# led-controller.net
KiCad netlist of a schematic drawn in EAGLE
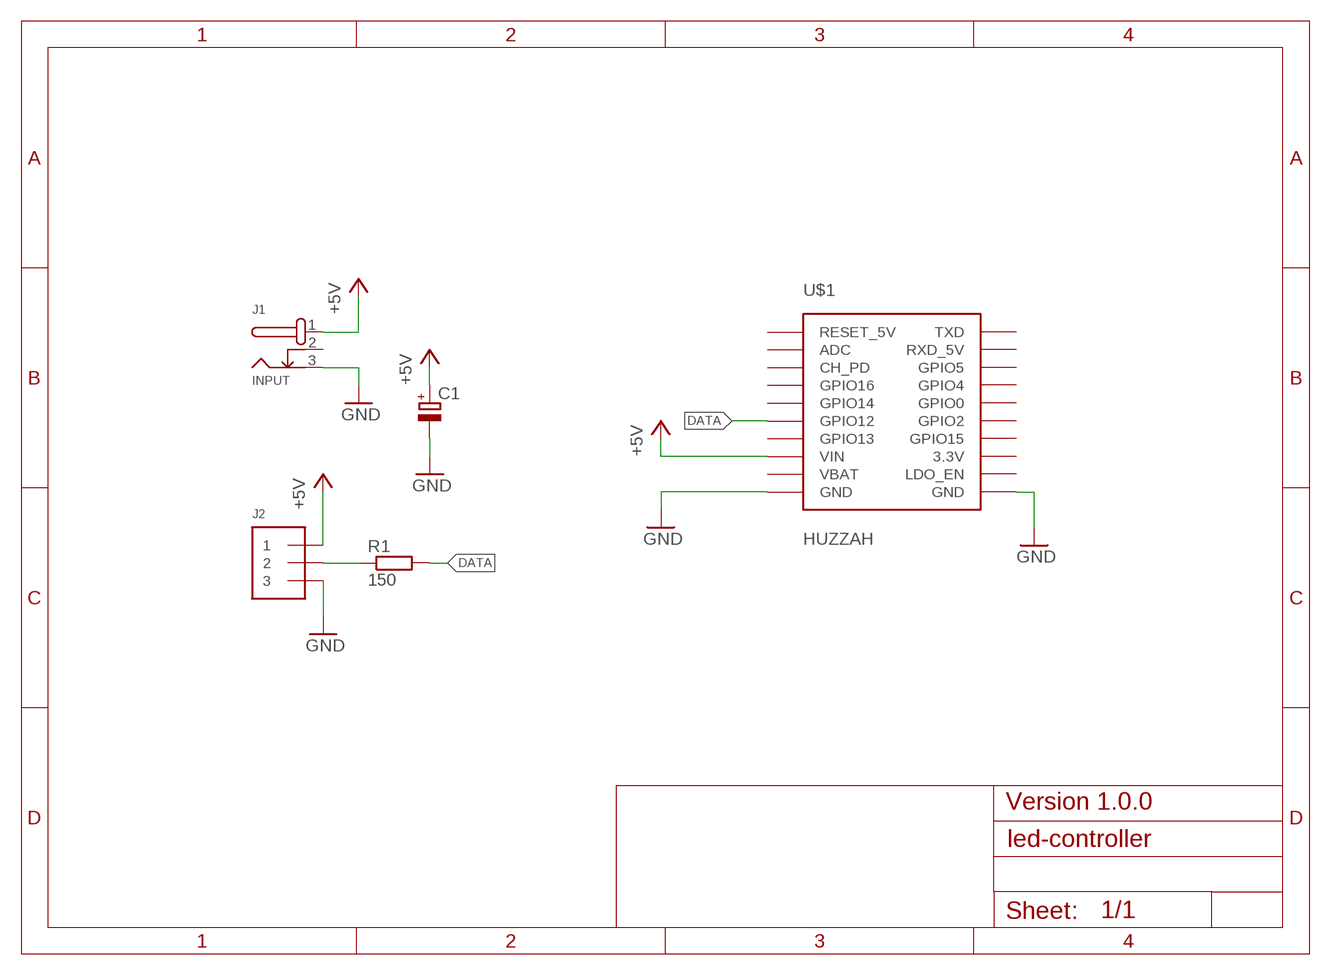
[diagram p0: schematic, sheet 1]

(export (version "E")
  (design (tool "Eeschema 10.0.6"))
  (components
    (comp (ref "C1")
      (value "CPOL-EUE7.5-16")
      (footprint "eagle-import:E7,5-16")
      (libsource (lib "eagle-import") (part "CPOL-EUE7.5-16"))
    )
    (comp (ref "J1")
      (value "INPUT")
      (footprint "eagle-import:DC10")
      (libsource (lib "eagle-import") (part "DC10PTH"))
    )
    (comp (ref "J2")
      (value "3,5MM-1X3-TERMBLOCK")
      (footprint "eagle-import:3,5MM-1X3-TERMBLOCK")
      (libsource (lib "eagle-import") (part "3,5MM-1X3-TERMBLOCK"))
    )
    (comp (ref "R1")
      (value "150")
      (footprint "eagle-import:R1206W")
      (libsource (lib "eagle-import") (part "R-EU_R1206W"))
    )
    (comp (ref "U$1")
      (value "HUZZAH")
      (footprint "eagle-import:HUZZAH")
      (libsource (lib "eagle-import") (part "HUZZAH"))
    )
  )
  (nets
    (net (code "1") (name "+5V") (class "Default")
      (node (ref "C1") (pin "+") (pinfunction "+_+") (pintype "passive"))
      (node (ref "J1") (pin "1") (pinfunction "1_1") (pintype "power_in"))
      (node (ref "J2") (pin "1") (pinfunction "1_1") (pintype "bidirectional"))
      (node (ref "U$1") (pin "VIN") (pinfunction "VIN_VIN") (pintype "bidirectional"))
    )
    (net (code "2") (name "/2") (class "Default")
      (node (ref "J1") (pin "2") (pinfunction "2_2") (pintype "power_in"))
    )
    (net (code "3") (name "DATA") (class "Default")
      (node (ref "R1") (pin "2") (pinfunction "2_2") (pintype "passive"))
      (node (ref "U$1") (pin "GPIO12") (pinfunction "GPIO12_GPIO12") (pintype "bidirectional"))
    )
    (net (code "4") (name "GND") (class "Default")
      (node (ref "C1") (pin "-") (pinfunction "-_-") (pintype "passive"))
      (node (ref "J1") (pin "3") (pinfunction "3_3") (pintype "power_in"))
      (node (ref "J2") (pin "3") (pinfunction "3_3") (pintype "bidirectional"))
      (node (ref "U$1") (pin "GND@1") (pinfunction "GND_GND@1") (pintype "bidirectional"))
      (node (ref "U$1") (pin "GND@2") (pinfunction "GND_GND@2") (pintype "bidirectional"))
    )
    (net (code "5") (name "Net-(J2-Pad2)") (class "Default")
      (node (ref "J2") (pin "2") (pinfunction "2_2") (pintype "bidirectional"))
      (node (ref "R1") (pin "1") (pinfunction "1_1") (pintype "passive"))
    )
    (net (code "6") (name "unconnected-(U$1-Pad3.3V)") (class "Default")
      (node (ref "U$1") (pin "3.3V") (pinfunction "3.3V_3.3V") (pintype "bidirectional"))
    )
    (net (code "7") (name "unconnected-(U$1-PadADC)") (class "Default")
      (node (ref "U$1") (pin "ADC") (pinfunction "ADC_ADC") (pintype "bidirectional"))
    )
    (net (code "8") (name "unconnected-(U$1-PadCH_PD)") (class "Default")
      (node (ref "U$1") (pin "CH_PD") (pinfunction "CH_PD_CH_PD") (pintype "bidirectional"))
    )
    (net (code "9") (name "unconnected-(U$1-PadGPIO0)") (class "Default")
      (node (ref "U$1") (pin "GPIO0") (pinfunction "GPIO0_GPIO0") (pintype "bidirectional"))
    )
    (net (code "10") (name "unconnected-(U$1-PadGPIO2)") (class "Default")
      (node (ref "U$1") (pin "GPIO2") (pinfunction "GPIO2_GPIO2") (pintype "bidirectional"))
    )
    (net (code "11") (name "unconnected-(U$1-PadGPIO4)") (class "Default")
      (node (ref "U$1") (pin "GPIO4") (pinfunction "GPIO4_GPIO4") (pintype "bidirectional"))
    )
    (net (code "12") (name "unconnected-(U$1-PadGPIO5)") (class "Default")
      (node (ref "U$1") (pin "GPIO5") (pinfunction "GPIO5_GPIO5") (pintype "bidirectional"))
    )
    (net (code "13") (name "unconnected-(U$1-PadGPIO13)") (class "Default")
      (node (ref "U$1") (pin "GPIO13") (pinfunction "GPIO13_GPIO13") (pintype "bidirectional"))
    )
    (net (code "14") (name "unconnected-(U$1-PadGPIO14)") (class "Default")
      (node (ref "U$1") (pin "GPIO14") (pinfunction "GPIO14_GPIO14") (pintype "bidirectional"))
    )
    (net (code "15") (name "unconnected-(U$1-PadGPIO15)") (class "Default")
      (node (ref "U$1") (pin "GPIO15") (pinfunction "GPIO15_GPIO15") (pintype "bidirectional"))
    )
    (net (code "16") (name "unconnected-(U$1-PadGPIO16)") (class "Default")
      (node (ref "U$1") (pin "GPIO16") (pinfunction "GPIO16_GPIO16") (pintype "bidirectional"))
    )
    (net (code "17") (name "unconnected-(U$1-PadLDO_EN)") (class "Default")
      (node (ref "U$1") (pin "LDO_EN") (pinfunction "LDO_EN_LDO_EN") (pintype "bidirectional"))
    )
    (net (code "18") (name "unconnected-(U$1-PadRESET_5V)") (class "Default")
      (node (ref "U$1") (pin "RESET_5V") (pinfunction "RESET_5V_RESET_5V") (pintype "bidirectional"))
    )
    (net (code "19") (name "unconnected-(U$1-PadRXD_5V)") (class "Default")
      (node (ref "U$1") (pin "RXD_5V") (pinfunction "RXD_5V_RXD_5V") (pintype "bidirectional"))
    )
    (net (code "20") (name "unconnected-(U$1-PadVBAT)") (class "Default")
      (node (ref "U$1") (pin "VBAT") (pinfunction "VBAT_VBAT") (pintype "bidirectional"))
    )
    (net (code "21") (name "unconnected-(U$1-TXD-PadTXD*1)") (class "Default")
      (node (ref "U$1") (pin "TXD*1") (pinfunction "TXD_TXD*1") (pintype "bidirectional"))
    )
  )
)
